# Inverter.net
KiCad netlist of a schematic drawn in Altium Designer
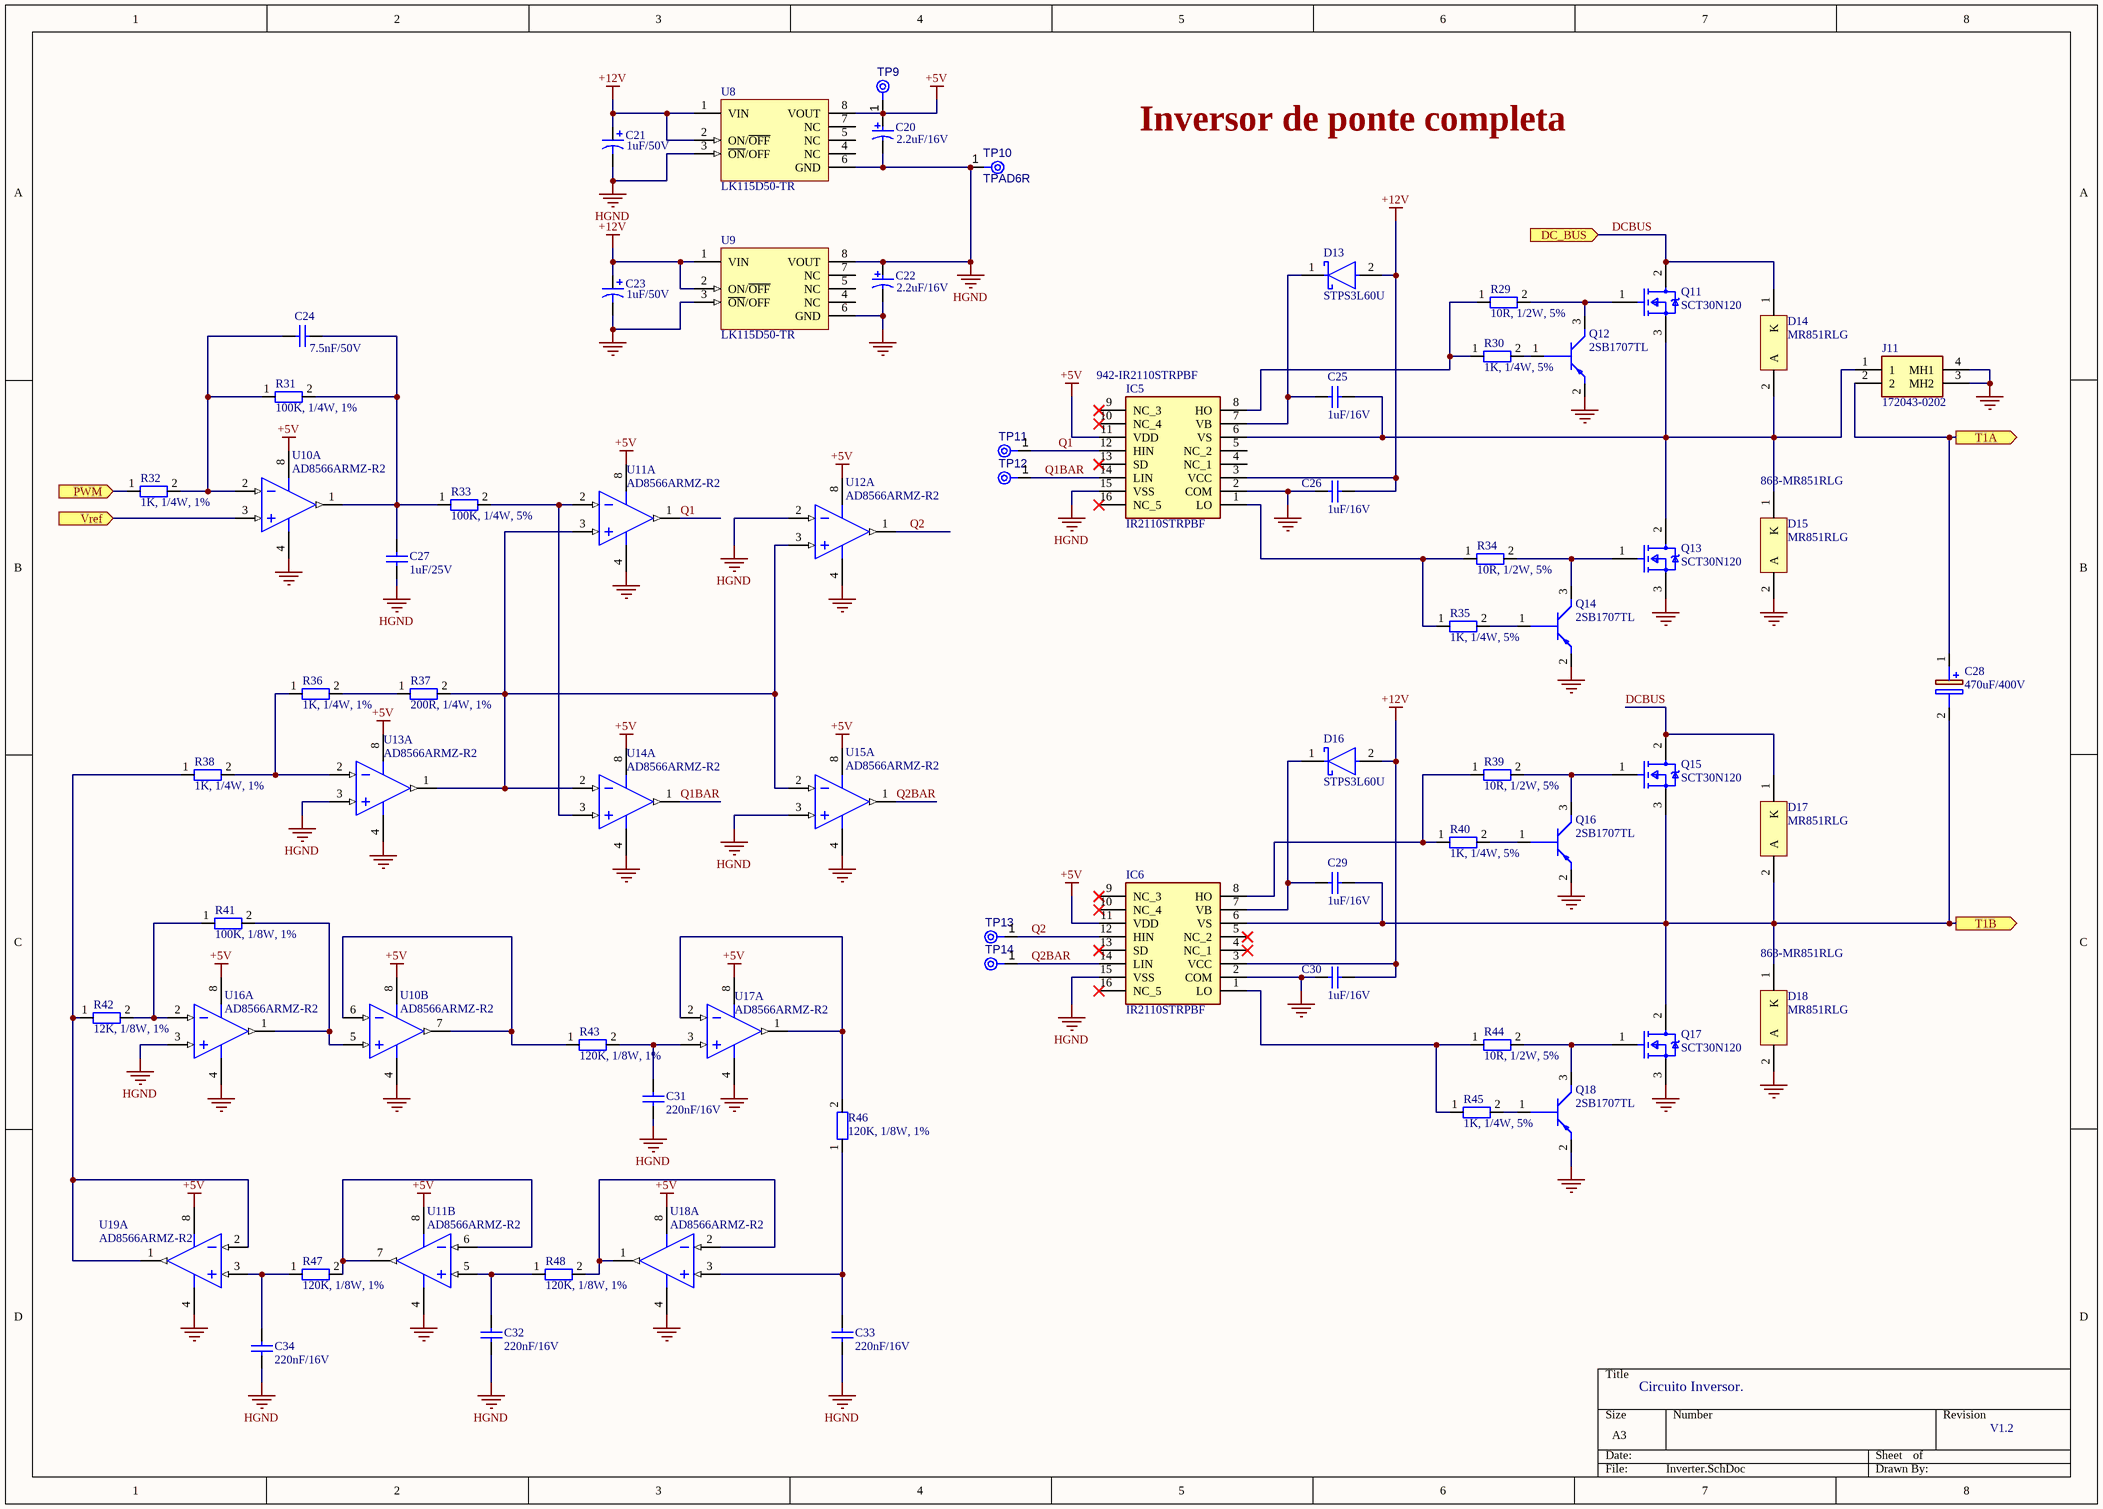
[diagram p0: Inverter.SchDoc]

(export (version "E")
  (design (tool "Eeschema 10.0.6"))
  (components
    (comp (ref "C20")
      (value "2.2uF/16V")
      (footprint "KEMT-T491-A_L")
      (description "Tantalum Capacitor, 2.2 uF, +/- 10%, 16 V, -55 to 125 degC, 2-Pin SMD, RoHS, Tape and Reel")
      (fields (field (name "VOLTAGE") "16VDC") (field (name "MANUFACTURER") "Kemet"))
      (libsource (lib "Altium Content Vault") (part "CAP-P-2"))
    )
    (comp (ref "C21")
      (value "1uF/50V")
      (footprint "C1206")
      (fields
        (field (name "MANUFACTURER") "KEMET")
        (field (name "MANUFACTURER PART NUMBER") "T491A105K050AT")
        (field (name "TOLERANCE") "10%")
        (field (name "PUBLISHER") "Altium Limited")
      )
      (libsource (lib "Miscellaneous Devices") (part "Cap Pol1"))
    )
    (comp (ref "C22")
      (value "2.2uF/16V")
      (footprint "KEMT-T491-A_L")
      (description "Tantalum Capacitor, 2.2 uF, +/- 10%, 16 V, -55 to 125 degC, 2-Pin SMD, RoHS, Tape and Reel")
      (fields (field (name "VOLTAGE") "16VDC") (field (name "MANUFACTURER") "Kemet"))
      (libsource (lib "Altium Content Vault") (part "CAP-P-2"))
    )
    (comp (ref "C23")
      (value "1uF/50V")
      (footprint "C1206")
      (fields
        (field (name "MANUFACTURER") "KEMET")
        (field (name "MANUFACTURER PART NUMBER") "T491A105K050AT")
        (field (name "TOLERANCE") "10%")
        (field (name "PUBLISHER") "Altium Limited")
      )
      (libsource (lib "Miscellaneous Devices") (part "Cap Pol1"))
    )
    (comp (ref "C24")
      (value "7.5nF/50V")
      (footprint "CAPC2013X135X45LL10T25")
      (fields
        (field (name "MANUFACTURER") "Murata")
        (field (name "PART NUMBER") "GRM21BR71H105KA12L")
        (field (name "MANUFACTURER PART NUMBER") "C0805C752FAGAC7210")
      )
      (libsource (lib "Altium Content Vault") (part "CAP"))
    )
    (comp (ref "C25")
      (value "1uF/16V")
      (footprint "CAPC2013X140X50ML20T25")
      (fields
        (field (name "PART NUMBER") "C0805C105Z4VACTU")
        (field (name "MANUFACTURER") "Kemet")
        (field (name "TOLERANCE") "80%")
      )
      (libsource (lib "Altium Content Vault") (part "CAP"))
    )
    (comp (ref "C26")
      (value "1uF/16V")
      (footprint "CAPC2013X140X50ML20T25")
      (fields
        (field (name "PART NUMBER") "C0805C105Z4VACTU")
        (field (name "MANUFACTURER") "Kemet")
        (field (name "TOLERANCE") "80%")
      )
      (libsource (lib "Altium Content Vault") (part "CAP"))
    )
    (comp (ref "C27")
      (value "1uF/25V")
      (footprint "CAPC2013X135X45LL10T25")
      (fields
        (field (name "MANUFACTURER") "KEMET")
        (field (name "MANUFACTURER PART NUMBER") "C0805C302K3GACTU")
        (field (name "TOLERANCE") "10%")
      )
      (libsource (lib "Altium Content Vault") (part "CAP"))
    )
    (comp (ref "C28")
      (value "470uF/400V")
      (footprint "PcbLib1:CAPPRD1000W210D3500H3700")
      (description "Capacitor Polarised")
      (fields
        (field (name "MANUFACTURER_PART_NUMBER") "MAL225966471E3")
        (field (name "MOUSER PART NUMBER") "594-MAL225966471E3")
      )
      (libsource (lib "*") (part "MAL225966471E3"))
    )
    (comp (ref "C29")
      (value "1uF/16V")
      (footprint "CAPC2013X140X50ML20T25")
      (fields
        (field (name "PART NUMBER") "C0805C105Z4VACTU")
        (field (name "MANUFACTURER") "Kemet")
        (field (name "TOLERANCE") "80%")
      )
      (libsource (lib "Altium Content Vault") (part "CAP"))
    )
    (comp (ref "C30")
      (value "1uF/16V")
      (footprint "CAPC2013X140X50ML20T25")
      (fields
        (field (name "PART NUMBER") "C0805C105Z4VACTU")
        (field (name "MANUFACTURER") "Kemet")
        (field (name "TOLERANCE") "80%")
      )
      (libsource (lib "Altium Content Vault") (part "CAP"))
    )
    (comp (ref "C31")
      (value "220nF/16V")
      (footprint "CAPC2013X135X45LL10T25")
      (fields (field (name "MANUFACTURER") "Murata") (field (name "PART NUMBER") "GRM21BR71H105KA12L"))
      (libsource (lib "Altium Content Vault") (part "CAP"))
    )
    (comp (ref "C32")
      (value "220nF/16V")
      (footprint "CAPC2013X135X45LL10T25")
      (fields (field (name "MANUFACTURER") "Murata") (field (name "PART NUMBER") "GRM21BR71H105KA12L"))
      (libsource (lib "Altium Content Vault") (part "CAP"))
    )
    (comp (ref "C33")
      (value "220nF/16V")
      (footprint "CAPC2013X135X45LL10T25")
      (fields (field (name "MANUFACTURER") "Murata") (field (name "PART NUMBER") "GRM21BR71H105KA12L"))
      (libsource (lib "Altium Content Vault") (part "CAP"))
    )
    (comp (ref "C34")
      (value "220nF/16V")
      (footprint "CAPC2013X135X45LL10T25")
      (fields (field (name "MANUFACTURER") "Murata") (field (name "PART NUMBER") "GRM21BR71H105KA12L"))
      (libsource (lib "Altium Content Vault") (part "CAP"))
    )
    (comp (ref "D13")
      (value "STPS3L60U")
      (footprint "FP-SMB-MFG")
      (description "DIODE SCHOTTKY 60V 3A SMB")
      (fields
        (field (name "OCTOPART") "https://octopart.com/stps3l60u-stmicroelectronics-334329")
        (field (name "MANUFACTURER") "STMicroelectronics")
      )
      (libsource (lib "Altium Content Vault") (part "fefb30dabb5d097ae2f038500735429"))
    )
    (comp (ref "D14")
      (value "MR851RLG")
      (footprint "ONSC-AXIAL_LEAD-2-267-05_V")
      (description "Fast Recovery Rectifier, 2-Pin Axial_Lead, Pb-Free, Tape and Reel")
      (fields (field (name "MANUFACTURER") "On Semiconductor"))
      (libsource (lib "Altium Content Vault") (part "ONSC-D-K1A2-2_A"))
    )
    (comp (ref "D15")
      (value "MR851RLG")
      (footprint "ONSC-AXIAL_LEAD-2-267-05_V")
      (description "Fast Recovery Rectifier, 2-Pin Axial_Lead, Pb-Free, Tape and Reel")
      (fields
        (field (name "MANUFACTURER") "On Semiconductor")
        (field (name "SUPPLIER PART NUMBER 1") "863-MR851RLG")
      )
      (libsource (lib "Altium Content Vault") (part "ONSC-D-K1A2-2_A"))
    )
    (comp (ref "D16")
      (value "STPS3L60U")
      (footprint "FP-SMB-MFG")
      (description "DIODE SCHOTTKY 60V 3A SMB")
      (fields
        (field (name "OCTOPART") "https://octopart.com/stps3l60u-stmicroelectronics-334329")
        (field (name "MANUFACTURER") "STMicroelectronics")
      )
      (libsource (lib "Altium Content Vault") (part "fefb30dabb5d097ae2f038500735429"))
    )
    (comp (ref "D17")
      (value "MR851RLG")
      (footprint "ONSC-AXIAL_LEAD-2-267-05_V")
      (description "Fast Recovery Rectifier, 2-Pin Axial_Lead, Pb-Free, Tape and Reel")
      (fields (field (name "MANUFACTURER") "On Semiconductor"))
      (libsource (lib "Altium Content Vault") (part "ONSC-D-K1A2-2_A"))
    )
    (comp (ref "D18")
      (value "MR851RLG")
      (footprint "ONSC-AXIAL_LEAD-2-267-05_V")
      (description "Fast Recovery Rectifier, 2-Pin Axial_Lead, Pb-Free, Tape and Reel")
      (fields
        (field (name "MANUFACTURER") "On Semiconductor")
        (field (name "SUPPLIER PART NUMBER 1") "863-MR851RLG")
      )
      (libsource (lib "Altium Content Vault") (part "ONSC-D-K1A2-2_A"))
    )
    (comp (ref "IC5")
      (value "IR2110STRPBF")
      (footprint "SOIC127P1032X265-16N")
      (description "MOSFET Driver 500 Volt 2.5A 2 Output Hi/Lo Side Non Input Volt 16-Pin SOIC W")
      (fields
        (field (name "MOUSER PART NUMBER") "942-IR2110STRPBF")
        (field (name "SUPPLIER PART NUMBER 1") "942-IR2110STRPBF")
        (field (name "MANUFACTURER") "International Rectifier")
      )
      (libsource (lib "pi2") (part "IR2110STRPBF"))
    )
    (comp (ref "IC6")
      (value "IR2110STRPBF")
      (footprint "SOIC127P1032X265-16N")
      (description "MOSFET Driver 500 Volt 2.5A 2 Output Hi/Lo Side Non Input Volt 16-Pin SOIC W")
      (fields
        (field (name "MOUSER PART NUMBER") "942-IR2110STRPBF")
        (field (name "MANUFACTURER") "International Rectifier")
      )
      (libsource (lib "pi2") (part "IR2110STRPBF"))
    )
    (comp (ref "J11")
      (value "172043-0202")
      (footprint "PcbLib1:1720430202")
      (description "CONN HDR 2POS 7.50MM R/A SLDR")
      (fields (field (name "MOUSER PART NUMBER") "538-172043-0202") (field (name "MANUFACTURER") "Molex"))
      (libsource (lib "pi2") (part "172043-0202"))
    )
    (comp (ref "Q11")
      (value "SCT30N120")
      (footprint "TO-247-3")
      (description "Trans MOSFET N-CH 1.2KV 45A 3-Pin HIP-247 Tube")
      (fields (field (name "MANUFACTURER") "STMicroelectronics"))
      (libsource (lib "pi2") (part "SCT30N120"))
    )
    (comp (ref "Q12")
      (value "2SB1707TL")
      (footprint "PcbLib1:SOT95P280X100-3N")
      (description "TRANS PNP 12V 4A TSMT3")
      (fields (field (name "MOUSER PART NUMBER") "755-2SB1707TL") (field (name "MANUFACTURER") "Rohm"))
      (libsource (lib "pi2") (part "2SB1707TL"))
    )
    (comp (ref "Q13")
      (value "SCT30N120")
      (footprint "TO-247-3")
      (description "Trans MOSFET N-CH 1.2KV 45A 3-Pin HIP-247 Tube")
      (fields (field (name "MANUFACTURER") "STMicroelectronics"))
      (libsource (lib "pi2") (part "SCT30N120"))
    )
    (comp (ref "Q14")
      (value "2SB1707TL")
      (footprint "PcbLib1:SOT95P280X100-3N")
      (description "TRANS PNP 12V 4A TSMT3")
      (fields (field (name "MOUSER PART NUMBER") "755-2SB1707TL") (field (name "MANUFACTURER") "Rohm"))
      (libsource (lib "pi2") (part "2SB1707TL"))
    )
    (comp (ref "Q15")
      (value "SCT30N120")
      (footprint "TO-247-3")
      (description "Trans MOSFET N-CH 1.2KV 45A 3-Pin HIP-247 Tube")
      (fields (field (name "MANUFACTURER") "STMicroelectronics"))
      (libsource (lib "pi2") (part "SCT30N120"))
    )
    (comp (ref "Q16")
      (value "2SB1707TL")
      (footprint "PcbLib1:SOT95P280X100-3N")
      (description "TRANS PNP 12V 4A TSMT3")
      (fields (field (name "MOUSER PART NUMBER") "755-2SB1707TL") (field (name "MANUFACTURER") "Rohm"))
      (libsource (lib "pi2") (part "2SB1707TL"))
    )
    (comp (ref "Q17")
      (value "SCT30N120")
      (footprint "TO-247-3")
      (description "Trans MOSFET N-CH 1.2KV 45A 3-Pin HIP-247 Tube")
      (fields (field (name "MANUFACTURER") "STMicroelectronics"))
      (libsource (lib "pi2") (part "SCT30N120"))
    )
    (comp (ref "Q18")
      (value "2SB1707TL")
      (footprint "PcbLib1:SOT95P280X100-3N")
      (description "TRANS PNP 12V 4A TSMT3")
      (fields (field (name "MOUSER PART NUMBER") "755-2SB1707TL") (field (name "MANUFACTURER") "Rohm"))
      (libsource (lib "pi2") (part "2SB1707TL"))
    )
    (comp (ref "R29")
      (value "10R, 1/2W, 5%")
      (footprint "RESC3216X60N")
      (description "Res Thick Film 0805 10 Ohm 5% 0.5W(1/2W) +/-200ppm/C Pad SMD Automotive T/R")
      (fields
        (field (name "MANUFACTURER") "Vishay Dale")
        (field (name "MANUFACTURER PART NUMBER") "CRCW080510R0JNEAHP")
      )
      (libsource (lib "pi2") (part "RES-1206"))
    )
    (comp (ref "R30")
      (value "1K, 1/4W, 5%")
      (footprint "PcbLib1:RES-0805")
      (description "Res Thick Film 0805 1K Ohm 5% 1/8W 100ppm/C Molded SMD SMD Paper T/R")
      (fields
        (field (name "MANUFACTURER_PART_NUMBER") "RC0805JR-131KL")
        (field (name "MOUSER PART NUMBER") "603-RC0805JR-131KL")
      )
      (libsource (lib "pi2") (part "Res-0805"))
    )
    (comp (ref "R31")
      (value "100K, 1/4W, 1%")
      (footprint "PcbLib1:RES-0805")
      (description "Thick Film Resistors 100K OHM 1%")
      (fields
        (field (name "MANUFACTURER_PART_NUMBER") "RC0805JR-131KL")
        (field (name "MOUSER PART NUMBER") "603-RC0805JR-131KL")
      )
      (libsource (lib "pi2") (part "Res-0805"))
    )
    (comp (ref "R32")
      (value "1K, 1/4W, 1%")
      (footprint "PcbLib1:RES-0805")
      (description "Res Thick Film 0805 1K Ohm 1% 1/8W 100ppm/C Molded SMD SMD Paper T/R")
      (fields
        (field (name "MANUFACTURER_PART_NUMBER") "RC0805JR-131KL")
        (field (name "MOUSER PART NUMBER") "603-RC0805JR-131KL")
      )
      (libsource (lib "pi2") (part "Res-0805"))
    )
    (comp (ref "R33")
      (value "100K, 1/4W, 5%")
      (footprint "PcbLib1:RES-0805")
      (description "Thick Film Resistors 100K OHM 1%")
      (fields
        (field (name "MANUFACTURER_PART_NUMBER") "RC0805JR-131KL")
        (field (name "MOUSER PART NUMBER") "603-RC0805JR-131KL")
      )
      (libsource (lib "pi2") (part "Res-0805"))
    )
    (comp (ref "R34")
      (value "10R, 1/2W, 5%")
      (footprint "RESC3216X60N")
      (description "Res Thick Film 0805 10 Ohm 5% 0.5W(1/2W) +/-200ppm/C Pad SMD Automotive T/R")
      (fields
        (field (name "MANUFACTURER") "Vishay Dale")
        (field (name "MANUFACTURER PART NUMBER") "CRCW080510R0JNEAHP")
      )
      (libsource (lib "pi2") (part "RES-1206"))
    )
    (comp (ref "R35")
      (value "1K, 1/4W, 5%")
      (footprint "PcbLib1:RES-0805")
      (description "Res Thick Film 0805 1K Ohm 5% 1/8W 100ppm/C Molded SMD SMD Paper T/R")
      (fields
        (field (name "MANUFACTURER_PART_NUMBER") "RC0805JR-131KL")
        (field (name "MOUSER PART NUMBER") "603-RC0805JR-131KL")
      )
      (libsource (lib "pi2") (part "Res-0805"))
    )
    (comp (ref "R36")
      (value "1K, 1/4W, 1%")
      (footprint "PcbLib1:RES-0805")
      (description "Res Thick Film 0805 1K Ohm 1% 1/8W 100ppm/C Molded SMD SMD Paper T/R")
      (fields
        (field (name "MANUFACTURER_PART_NUMBER") "RC0805JR-131KL")
        (field (name "MOUSER PART NUMBER") "603-RC0805JR-131KL")
      )
      (libsource (lib "pi2") (part "Res-0805"))
    )
    (comp (ref "R37")
      (value "200R, 1/4W, 1%")
      (footprint "PcbLib1:RES-0805")
      (description "Res Thick Film 2.0 x 1.2 mm 200 Ohm 1% 0.125W(1/8W) 100ppm/ C Molded SMD Paper T/R")
      (fields
        (field (name "MANUFACTURER_PART_NUMBER") "RC0805JR-131KL")
        (field (name "MOUSER PART NUMBER") "603-RC0805JR-131KL")
      )
      (libsource (lib "pi2") (part "Res-0805"))
    )
    (comp (ref "R38")
      (value "1K, 1/4W, 1%")
      (footprint "PcbLib1:RES-0805")
      (description "Res Thick Film 0805 1K Ohm 1% 1/8W 100ppm/C Molded SMD SMD Paper T/R")
      (fields
        (field (name "MANUFACTURER_PART_NUMBER") "RC0805JR-131KL")
        (field (name "MOUSER PART NUMBER") "603-RC0805JR-131KL")
      )
      (libsource (lib "pi2") (part "Res-0805"))
    )
    (comp (ref "R39")
      (value "10R, 1/2W, 5%")
      (footprint "RESC3216X60N")
      (description "Res Thick Film 0805 10 Ohm 5% 0.5W(1/2W) +/-200ppm/C Pad SMD Automotive T/R")
      (fields
        (field (name "MANUFACTURER") "Vishay Dale")
        (field (name "MANUFACTURER PART NUMBER") "CRCW080510R0JNEAHP")
      )
      (libsource (lib "pi2") (part "RES-1206"))
    )
    (comp (ref "R40")
      (value "1K, 1/4W, 5%")
      (footprint "PcbLib1:RES-0805")
      (description "Res Thick Film 0805 1K Ohm 5% 1/8W 100ppm/C Molded SMD SMD Paper T/R")
      (fields
        (field (name "MANUFACTURER_PART_NUMBER") "RC0805JR-131KL")
        (field (name "MOUSER PART NUMBER") "603-RC0805JR-131KL")
      )
      (libsource (lib "pi2") (part "Res-0805"))
    )
    (comp (ref "R41")
      (value "100K, 1/8W, 1%")
      (footprint "PcbLib1:RES-0805")
      (description "Thick Film Resistors 100K OHM 1%")
      (fields
        (field (name "MANUFACTURER_PART_NUMBER") "RC0805JR-131KL")
        (field (name "MOUSER PART NUMBER") "603-RC0805JR-131KL")
      )
      (libsource (lib "pi2") (part "Res-0805"))
    )
    (comp (ref "R42")
      (value "12K, 1/8W, 1%")
      (footprint "PcbLib1:RES-0805")
      (description "Res Thick Film 0805 12K Ohm 1% 0.125W(1/8W) ±100ppm/C Molded SMD Paper T/R")
      (fields
        (field (name "MANUFACTURER_PART_NUMBER") "RC0805JR-131KL")
        (field (name "MOUSER PART NUMBER") "603-RC0805JR-131KL")
      )
      (libsource (lib "pi2") (part "Res-0805"))
    )
    (comp (ref "R43")
      (value "120K, 1/8W, 1%")
      (footprint "PcbLib1:RES-0805")
      (description "YAGEO - RC0805FR-07120KL - RES, 120K, 1%, 0.125W, 0805, THICK FILM")
      (fields
        (field (name "MANUFACTURER_PART_NUMBER") "RC0805JR-131KL")
        (field (name "MOUSER PART NUMBER") "603-RC0805JR-131KL")
      )
      (libsource (lib "pi2") (part "Res-0805"))
    )
    (comp (ref "R44")
      (value "10R, 1/2W, 5%")
      (footprint "RESC3216X60N")
      (description "Res Thick Film 0805 10 Ohm 5% 0.5W(1/2W) +/-200ppm/C Pad SMD Automotive T/R")
      (fields
        (field (name "MANUFACTURER") "Vishay Dale")
        (field (name "MANUFACTURER PART NUMBER") "CRCW080510R0JNEAHP")
      )
      (libsource (lib "pi2") (part "RES-1206"))
    )
    (comp (ref "R45")
      (value "1K, 1/4W, 5%")
      (footprint "PcbLib1:RES-0805")
      (description "Res Thick Film 0805 1K Ohm 5% 1/8W 100ppm/C Molded SMD SMD Paper T/R")
      (fields
        (field (name "MANUFACTURER_PART_NUMBER") "RC0805JR-131KL")
        (field (name "MOUSER PART NUMBER") "603-RC0805JR-131KL")
      )
      (libsource (lib "pi2") (part "Res-0805"))
    )
    (comp (ref "R46")
      (value "120K, 1/8W, 1%")
      (footprint "PcbLib1:RES-0805")
      (description "YAGEO - RC0805FR-07120KL - RES, 120K, 1%, 0.125W, 0805, THICK FILM")
      (fields
        (field (name "MANUFACTURER_PART_NUMBER") "RC0805JR-131KL")
        (field (name "MOUSER PART NUMBER") "603-RC0805JR-131KL")
      )
      (libsource (lib "") (part "Res-0805_1"))
    )
    (comp (ref "R47")
      (value "120K, 1/8W, 1%")
      (footprint "PcbLib1:RES-0805")
      (description "YAGEO - RC0805FR-07120KL - RES, 120K, 1%, 0.125W, 0805, THICK FILM")
      (fields
        (field (name "MANUFACTURER_PART_NUMBER") "RC0805JR-131KL")
        (field (name "MOUSER PART NUMBER") "603-RC0805JR-131KL")
      )
      (libsource (lib "pi2") (part "Res-0805"))
    )
    (comp (ref "R48")
      (value "120K, 1/8W, 1%")
      (footprint "PcbLib1:RES-0805")
      (description "YAGEO - RC0805FR-07120KL - RES, 120K, 1%, 0.125W, 0805, THICK FILM")
      (fields
        (field (name "MANUFACTURER_PART_NUMBER") "RC0805JR-131KL")
        (field (name "MOUSER PART NUMBER") "603-RC0805JR-131KL")
      )
      (libsource (lib "pi2") (part "Res-0805"))
    )
    (comp (ref "TP9")
      (value "TPAD6R")
      (footprint "TP06R")
      (description "0.6mm round")
      (libsource (lib "PI2") (part "CMP-001-0001-4"))
    )
    (comp (ref "TP10")
      (value "TPAD6R")
      (footprint "TP06R")
      (description "0.6mm round")
      (libsource (lib "PI2") (part "CMP-001-0001-4"))
    )
    (comp (ref "TP11")
      (value "TPAD6R")
      (footprint "TP06R")
      (description "0.6mm round")
      (libsource (lib "PI2") (part "CMP-001-0001-4"))
    )
    (comp (ref "TP12")
      (value "TPAD6R")
      (footprint "TP06R")
      (description "0.6mm round")
      (libsource (lib "PI2") (part "CMP-001-0001-4"))
    )
    (comp (ref "TP13")
      (value "TPAD6R")
      (footprint "TP06R")
      (description "0.6mm round")
      (libsource (lib "PI2") (part "CMP-001-0001-4"))
    )
    (comp (ref "TP14")
      (value "TPAD6R")
      (footprint "TP06R")
      (description "0.6mm round")
      (libsource (lib "PI2") (part "CMP-001-0001-4"))
    )
    (comp (ref "U8")
      (value "LK115D50-TR")
      (footprint "SO8_M")
      (description "100mA, Very Low Drop (0.2V) with Inhibit Voltage Regulator, 5V, 8-Pin SO, Tape and Reel")
      (fields (field (name "MANUFACTURER") "STMicroelectronics"))
      (libsource (lib "Altium Content Vault") (part "PM-REG-LK115D-IL8"))
    )
    (comp (ref "U9")
      (value "LK115D50-TR")
      (footprint "SO8_M")
      (description "100mA, Very Low Drop (0.2V) with Inhibit Voltage Regulator, 5V, 8-Pin SO, Tape and Reel")
      (fields (field (name "MANUFACTURER") "STMicroelectronics"))
      (libsource (lib "Altium Content Vault") (part "PM-REG-LK115D-IL8"))
    )
    (comp (ref "U10")
      (value "AD8566ARMZ-R2")
      (footprint "ADI-RM-8_L")
      (fields (field (name "MANUFACTURER") "Analog Devices") (field (name "GENERIC PART NUMBER") "AD8566"))
      (libsource (lib "Altium Content Vault") (part "ADI-ADA4000-2-X-8"))
    )
    (comp (ref "U11")
      (value "AD8566ARMZ-R2")
      (footprint "ADI-RM-8_L")
      (fields (field (name "MANUFACTURER") "Analog Devices") (field (name "GENERIC PART NUMBER") "AD8566"))
      (libsource (lib "Altium Content Vault") (part "ADI-ADA4000-2-X-8"))
    )
    (comp (ref "U12")
      (value "AD8566ARMZ-R2")
      (footprint "ADI-RM-8_L")
      (fields (field (name "MANUFACTURER") "Analog Devices") (field (name "GENERIC PART NUMBER") "AD8566"))
      (libsource (lib "Altium Content Vault") (part "ADI-ADA4000-2-X-8"))
    )
    (comp (ref "U13")
      (value "AD8566ARMZ-R2")
      (footprint "ADI-RM-8_L")
      (fields (field (name "MANUFACTURER") "Analog Devices") (field (name "GENERIC PART NUMBER") "AD8566"))
      (libsource (lib "Altium Content Vault") (part "ADI-ADA4000-2-X-8"))
    )
    (comp (ref "U14")
      (value "AD8566ARMZ-R2")
      (footprint "ADI-RM-8_L")
      (fields (field (name "MANUFACTURER") "Analog Devices") (field (name "GENERIC PART NUMBER") "AD8566"))
      (libsource (lib "Altium Content Vault") (part "ADI-ADA4000-2-X-8"))
    )
    (comp (ref "U15")
      (value "AD8566ARMZ-R2")
      (footprint "ADI-RM-8_L")
      (fields (field (name "MANUFACTURER") "Analog Devices") (field (name "GENERIC PART NUMBER") "AD8566"))
      (libsource (lib "Altium Content Vault") (part "ADI-ADA4000-2-X-8"))
    )
    (comp (ref "U16")
      (value "AD8566ARMZ-R2")
      (footprint "ADI-RM-8_L")
      (fields (field (name "MANUFACTURER") "Analog Devices") (field (name "GENERIC PART NUMBER") "AD8566"))
      (libsource (lib "Altium Content Vault") (part "ADI-ADA4000-2-X-8"))
    )
    (comp (ref "U17")
      (value "AD8566ARMZ-R2")
      (footprint "ADI-RM-8_L")
      (fields (field (name "MANUFACTURER") "Analog Devices") (field (name "GENERIC PART NUMBER") "AD8566"))
      (libsource (lib "Altium Content Vault") (part "ADI-ADA4000-2-X-8"))
    )
    (comp (ref "U18")
      (value "AD8566ARMZ-R2")
      (footprint "ADI-RM-8_L")
      (fields (field (name "MANUFACTURER") "Analog Devices") (field (name "GENERIC PART NUMBER") "AD8566"))
      (libsource (lib "Altium Content Vault") (part "ADI-ADA4000-2-X-8"))
    )
    (comp (ref "U19")
      (value "AD8566ARMZ-R2")
      (footprint "ADI-RM-8_L")
      (fields (field (name "MANUFACTURER") "Analog Devices") (field (name "GENERIC PART NUMBER") "AD8566"))
      (libsource (lib "Altium Content Vault") (part "ADI-ADA4000-2-X-8"))
    )
  )
  (nets
    (net (code "1") (name "+5V") (class "Default")
      (node (ref "C20") (pin "1") (pinfunction "1_1") (pintype "passive"))
      (node (ref "IC5") (pin "11") (pinfunction "VDD_11") (pintype "passive"))
      (node (ref "IC6") (pin "11") (pinfunction "VDD_11") (pintype "passive"))
      (node (ref "TP9") (pin "1") (pinfunction "TP_1") (pintype "passive"))
      (node (ref "U10") (pin "8") (pinfunction "+V_8") (pintype "power_in"))
      (node (ref "U11") (pin "8") (pinfunction "+V_8") (pintype "power_in"))
      (node (ref "U12") (pin "8") (pinfunction "+V_8") (pintype "power_in"))
      (node (ref "U13") (pin "8") (pinfunction "+V_8") (pintype "power_in"))
      (node (ref "U14") (pin "8") (pinfunction "+V_8") (pintype "power_in"))
      (node (ref "U15") (pin "8") (pinfunction "+V_8") (pintype "power_in"))
      (node (ref "U16") (pin "8") (pinfunction "+V_8") (pintype "power_in"))
      (node (ref "U17") (pin "8") (pinfunction "+V_8") (pintype "power_in"))
      (node (ref "U18") (pin "8") (pinfunction "+V_8") (pintype "power_in"))
      (node (ref "U19") (pin "8") (pinfunction "+V_8") (pintype "power_in"))
      (node (ref "U8") (pin "8") (pinfunction "VOUT_8") (pintype "power_in"))
    )
    (net (code "2") (name "+12V") (class "Default")
      (node (ref "C21") (pin "1") (pinfunction "1_1") (pintype "passive"))
      (node (ref "C23") (pin "1") (pinfunction "1_1") (pintype "passive"))
      (node (ref "C26") (pin "2") (pinfunction "2_2") (pintype "passive"))
      (node (ref "C30") (pin "1") (pinfunction "1_1") (pintype "passive"))
      (node (ref "D13") (pin "2") (pinfunction "A_2") (pintype "passive"))
      (node (ref "D16") (pin "2") (pinfunction "A_2") (pintype "passive"))
      (node (ref "IC5") (pin "3") (pinfunction "VCC_3") (pintype "passive"))
      (node (ref "IC6") (pin "3") (pinfunction "VCC_3") (pintype "passive"))
      (node (ref "U8") (pin "1") (pinfunction "VIN_1") (pintype "power_in"))
      (node (ref "U8") (pin "2") (pinfunction "ON/~{OFF}_2") (pintype "input"))
      (node (ref "U9") (pin "1") (pinfunction "VIN_1") (pintype "power_in"))
      (node (ref "U9") (pin "2") (pinfunction "ON/~{OFF}_2") (pintype "input"))
    )
    (net (code "3") (name "/DCBUS") (class "Default")
      (node (ref "D14") (pin "1") (pinfunction "K_1") (pintype "passive"))
      (node (ref "D17") (pin "1") (pinfunction "K_1") (pintype "passive"))
      (node (ref "Q11") (pin "2") (pinfunction "D_2") (pintype "passive"))
      (node (ref "Q15") (pin "2") (pinfunction "D_2") (pintype "passive"))
    )
    (net (code "4") (name "/PWM") (class "Default")
      (node (ref "R32") (pin "1") (pinfunction "1_1") (pintype "passive"))
    )
    (net (code "5") (name "/Q1") (class "Default")
      (node (ref "IC5") (pin "12") (pinfunction "HIN_12") (pintype "passive"))
      (node (ref "TP11") (pin "1") (pinfunction "TP_1") (pintype "passive"))
      (node (ref "U11") (pin "1") (pinfunction "OUT_A_1") (pintype "output"))
    )
    (net (code "6") (name "/Q1BAR") (class "Default")
      (node (ref "IC5") (pin "14") (pinfunction "LIN_14") (pintype "passive"))
      (node (ref "TP12") (pin "1") (pinfunction "TP_1") (pintype "passive"))
      (node (ref "U14") (pin "1") (pinfunction "OUT_A_1") (pintype "output"))
    )
    (net (code "7") (name "/Q2") (class "Default")
      (node (ref "IC6") (pin "12") (pinfunction "HIN_12") (pintype "passive"))
      (node (ref "TP13") (pin "1") (pinfunction "TP_1") (pintype "passive"))
      (node (ref "U12") (pin "1") (pinfunction "OUT_A_1") (pintype "output"))
    )
    (net (code "8") (name "/Q2BAR") (class "Default")
      (node (ref "IC6") (pin "14") (pinfunction "LIN_14") (pintype "passive"))
      (node (ref "TP14") (pin "1") (pinfunction "TP_1") (pintype "passive"))
      (node (ref "U15") (pin "1") (pinfunction "OUT_A_1") (pintype "output"))
    )
    (net (code "9") (name "/T1A") (class "Default")
      (node (ref "C28") (pin "1") (pinfunction "+_1") (pintype "passive"))
      (node (ref "J11") (pin "2") (pinfunction "2_2") (pintype "passive"))
    )
    (net (code "10") (name "/T1B") (class "Default")
      (node (ref "C28") (pin "2") (pinfunction "-_2") (pintype "passive"))
      (node (ref "C29") (pin "1") (pinfunction "1_1") (pintype "passive"))
      (node (ref "D17") (pin "2") (pinfunction "A_2") (pintype "passive"))
      (node (ref "D18") (pin "1") (pinfunction "K_1") (pintype "passive"))
      (node (ref "IC6") (pin "6") (pinfunction "VS_6") (pintype "passive"))
      (node (ref "Q15") (pin "3") (pinfunction "S_3") (pintype "passive"))
      (node (ref "Q17") (pin "2") (pinfunction "D_2") (pintype "passive"))
    )
    (net (code "11") (name "/Vref") (class "Default")
      (node (ref "U10") (pin "3") (pinfunction "+IN_A_3") (pintype "input"))
    )
    (net (code "12") (name "GND") (class "Default")
      (node (ref "C22") (pin "2") (pinfunction "2_2") (pintype "passive"))
      (node (ref "C23") (pin "2") (pinfunction "2_2") (pintype "passive"))
      (node (ref "C26") (pin "1") (pinfunction "1_1") (pintype "passive"))
      (node (ref "C30") (pin "2") (pinfunction "2_2") (pintype "passive"))
      (node (ref "D15") (pin "2") (pinfunction "A_2") (pintype "passive"))
      (node (ref "D18") (pin "2") (pinfunction "A_2") (pintype "passive"))
      (node (ref "IC5") (pin "2") (pinfunction "COM_2") (pintype "passive"))
      (node (ref "IC6") (pin "2") (pinfunction "COM_2") (pintype "passive"))
      (node (ref "J11") (pin "3") (pinfunction "MH2_3") (pintype "passive"))
      (node (ref "J11") (pin "4") (pinfunction "MH1_4") (pintype "passive"))
      (node (ref "Q12") (pin "2") (pinfunction "E_2") (pintype "passive"))
      (node (ref "Q13") (pin "3") (pinfunction "S_3") (pintype "passive"))
      (node (ref "Q14") (pin "2") (pinfunction "E_2") (pintype "passive"))
      (node (ref "Q16") (pin "2") (pinfunction "E_2") (pintype "passive"))
      (node (ref "Q17") (pin "3") (pinfunction "S_3") (pintype "passive"))
      (node (ref "Q18") (pin "2") (pinfunction "E_2") (pintype "passive"))
      (node (ref "U10") (pin "4") (pinfunction "-V_4") (pintype "power_in"))
      (node (ref "U11") (pin "4") (pinfunction "-V_4") (pintype "power_in"))
      (node (ref "U12") (pin "4") (pinfunction "-V_4") (pintype "power_in"))
      (node (ref "U13") (pin "4") (pinfunction "-V_4") (pintype "power_in"))
      (node (ref "U14") (pin "4") (pinfunction "-V_4") (pintype "power_in"))
      (node (ref "U15") (pin "4") (pinfunction "-V_4") (pintype "power_in"))
      (node (ref "U16") (pin "4") (pinfunction "-V_4") (pintype "power_in"))
      (node (ref "U17") (pin "4") (pinfunction "-V_4") (pintype "power_in"))
      (node (ref "U18") (pin "4") (pinfunction "-V_4") (pintype "power_in"))
      (node (ref "U19") (pin "4") (pinfunction "-V_4") (pintype "power_in"))
      (node (ref "U9") (pin "3") (pinfunction "~{ON}/OFF_3") (pintype "input"))
      (node (ref "U9") (pin "6") (pinfunction "GND_6") (pintype "power_in"))
    )
    (net (code "13") (name "HGND") (class "Default")
      (node (ref "C20") (pin "2") (pinfunction "2_2") (pintype "passive"))
      (node (ref "C21") (pin "2") (pinfunction "2_2") (pintype "passive"))
      (node (ref "C22") (pin "1") (pinfunction "1_1") (pintype "passive"))
      (node (ref "C27") (pin "1") (pinfunction "1_1") (pintype "passive"))
      (node (ref "C31") (pin "1") (pinfunction "1_1") (pintype "passive"))
      (node (ref "C32") (pin "1") (pinfunction "1_1") (pintype "passive"))
      (node (ref "C33") (pin "1") (pinfunction "1_1") (pintype "passive"))
      (node (ref "C34") (pin "1") (pinfunction "1_1") (pintype "passive"))
      (node (ref "IC5") (pin "15") (pinfunction "VSS_15") (pintype "passive"))
      (node (ref "IC6") (pin "15") (pinfunction "VSS_15") (pintype "passive"))
      (node (ref "TP10") (pin "1") (pinfunction "TP_1") (pintype "passive"))
      (node (ref "U12") (pin "2") (pinfunction "-IN_A_2") (pintype "input"))
      (node (ref "U13") (pin "3") (pinfunction "+IN_A_3") (pintype "input"))
      (node (ref "U15") (pin "3") (pinfunction "+IN_A_3") (pintype "input"))
      (node (ref "U16") (pin "3") (pinfunction "+IN_A_3") (pintype "input"))
      (node (ref "U8") (pin "3") (pinfunction "~{ON}/OFF_3") (pintype "input"))
      (node (ref "U8") (pin "6") (pinfunction "GND_6") (pintype "power_in"))
      (node (ref "U9") (pin "8") (pinfunction "VOUT_8") (pintype "power_in"))
    )
    (net (code "14") (name "Net-(D13-K)") (class "Default")
      (node (ref "C25") (pin "1") (pinfunction "1_1") (pintype "passive"))
      (node (ref "D13") (pin "1") (pinfunction "K_1") (pintype "passive"))
      (node (ref "IC5") (pin "7") (pinfunction "VB_7") (pintype "passive"))
    )
    (net (code "15") (name "Net-(D14-A)") (class "Default")
      (node (ref "C25") (pin "2") (pinfunction "2_2") (pintype "passive"))
      (node (ref "D14") (pin "2") (pinfunction "A_2") (pintype "passive"))
      (node (ref "D15") (pin "1") (pinfunction "K_1") (pintype "passive"))
      (node (ref "IC5") (pin "6") (pinfunction "VS_6") (pintype "passive"))
      (node (ref "J11") (pin "1") (pinfunction "1_1") (pintype "passive"))
      (node (ref "Q11") (pin "3") (pinfunction "S_3") (pintype "passive"))
      (node (ref "Q13") (pin "2") (pinfunction "D_2") (pintype "passive"))
    )
    (net (code "16") (name "Net-(D16-K)") (class "Default")
      (node (ref "C29") (pin "2") (pinfunction "2_2") (pintype "passive"))
      (node (ref "D16") (pin "1") (pinfunction "K_1") (pintype "passive"))
      (node (ref "IC6") (pin "7") (pinfunction "VB_7") (pintype "passive"))
    )
    (net (code "17") (name "Net-(IC5-HO)") (class "Default")
      (node (ref "IC5") (pin "8") (pinfunction "HO_8") (pintype "passive"))
      (node (ref "R29") (pin "1") (pinfunction "1_1") (pintype "passive"))
      (node (ref "R30") (pin "1") (pinfunction "1_1") (pintype "passive"))
    )
    (net (code "18") (name "Net-(IC5-LO)") (class "Default")
      (node (ref "IC5") (pin "1") (pinfunction "LO_1") (pintype "passive"))
      (node (ref "R34") (pin "1") (pinfunction "1_1") (pintype "passive"))
      (node (ref "R35") (pin "1") (pinfunction "1_1") (pintype "passive"))
    )
    (net (code "19") (name "Net-(IC6-HO)") (class "Default")
      (node (ref "IC6") (pin "8") (pinfunction "HO_8") (pintype "passive"))
      (node (ref "R39") (pin "1") (pinfunction "1_1") (pintype "passive"))
      (node (ref "R40") (pin "1") (pinfunction "1_1") (pintype "passive"))
    )
    (net (code "20") (name "Net-(IC6-LO)") (class "Default")
      (node (ref "IC6") (pin "1") (pinfunction "LO_1") (pintype "passive"))
      (node (ref "R44") (pin "1") (pinfunction "1_1") (pintype "passive"))
      (node (ref "R45") (pin "1") (pinfunction "1_1") (pintype "passive"))
    )
    (net (code "21") (name "Net-(Q11-G)") (class "Default")
      (node (ref "Q11") (pin "1") (pinfunction "G_1") (pintype "passive"))
      (node (ref "Q12") (pin "3") (pinfunction "C_3") (pintype "passive"))
      (node (ref "R29") (pin "2") (pinfunction "2_2") (pintype "passive"))
    )
    (net (code "22") (name "Net-(Q12-B)") (class "Default")
      (node (ref "Q12") (pin "1") (pinfunction "B_1") (pintype "passive"))
      (node (ref "R30") (pin "2") (pinfunction "2_2") (pintype "passive"))
    )
    (net (code "23") (name "Net-(Q13-G)") (class "Default")
      (node (ref "Q13") (pin "1") (pinfunction "G_1") (pintype "passive"))
      (node (ref "Q14") (pin "3") (pinfunction "C_3") (pintype "passive"))
      (node (ref "R34") (pin "2") (pinfunction "2_2") (pintype "passive"))
    )
    (net (code "24") (name "Net-(Q14-B)") (class "Default")
      (node (ref "Q14") (pin "1") (pinfunction "B_1") (pintype "passive"))
      (node (ref "R35") (pin "2") (pinfunction "2_2") (pintype "passive"))
    )
    (net (code "25") (name "Net-(Q15-G)") (class "Default")
      (node (ref "Q15") (pin "1") (pinfunction "G_1") (pintype "passive"))
      (node (ref "Q16") (pin "3") (pinfunction "C_3") (pintype "passive"))
      (node (ref "R39") (pin "2") (pinfunction "2_2") (pintype "passive"))
    )
    (net (code "26") (name "Net-(Q16-B)") (class "Default")
      (node (ref "Q16") (pin "1") (pinfunction "B_1") (pintype "passive"))
      (node (ref "R40") (pin "2") (pinfunction "2_2") (pintype "passive"))
    )
    (net (code "27") (name "Net-(Q17-G)") (class "Default")
      (node (ref "Q17") (pin "1") (pinfunction "G_1") (pintype "passive"))
      (node (ref "Q18") (pin "3") (pinfunction "C_3") (pintype "passive"))
      (node (ref "R44") (pin "2") (pinfunction "2_2") (pintype "passive"))
    )
    (net (code "28") (name "Net-(Q18-B)") (class "Default")
      (node (ref "Q18") (pin "1") (pinfunction "B_1") (pintype "passive"))
      (node (ref "R45") (pin "2") (pinfunction "2_2") (pintype "passive"))
    )
    (net (code "29") (name "Net-(R36-Pad2)") (class "Default")
      (node (ref "R36") (pin "2") (pinfunction "2_2") (pintype "passive"))
      (node (ref "R37") (pin "1") (pinfunction "1_1") (pintype "passive"))
    )
    (net (code "30") (name "Net-(U10A--IN_A)") (class "Default")
      (node (ref "C24") (pin "2") (pinfunction "2_2") (pintype "passive"))
      (node (ref "R31") (pin "1") (pinfunction "1_1") (pintype "passive"))
      (node (ref "R32") (pin "2") (pinfunction "2_2") (pintype "passive"))
      (node (ref "U10") (pin "2") (pinfunction "-IN_A_2") (pintype "input"))
    )
    (net (code "31") (name "Net-(U10A-OUT_A)") (class "Default")
      (node (ref "C24") (pin "1") (pinfunction "1_1") (pintype "passive"))
      (node (ref "C27") (pin "2") (pinfunction "2_2") (pintype "passive"))
      (node (ref "R31") (pin "2") (pinfunction "2_2") (pintype "passive"))
      (node (ref "R33") (pin "1") (pinfunction "1_1") (pintype "passive"))
      (node (ref "U10") (pin "1") (pinfunction "OUT_A_1") (pintype "output"))
    )
    (net (code "32") (name "Net-(U10B-+IN_B)") (class "Default")
      (node (ref "R41") (pin "2") (pinfunction "2_2") (pintype "passive"))
      (node (ref "U10") (pin "5") (pinfunction "+IN_B_5") (pintype "input"))
      (node (ref "U16") (pin "1") (pinfunction "OUT_A_1") (pintype "output"))
    )
    (net (code "33") (name "Net-(U10B--IN_B)") (class "Default")
      (node (ref "R43") (pin "1") (pinfunction "1_1") (pintype "passive"))
      (node (ref "U10") (pin "6") (pinfunction "-IN_B_6") (pintype "input"))
      (node (ref "U10") (pin "7") (pinfunction "OUT_B_7") (pintype "output"))
    )
    (net (code "34") (name "Net-(U11A-+IN_A)") (class "Default")
      (node (ref "R37") (pin "2") (pinfunction "2_2") (pintype "passive"))
      (node (ref "U11") (pin "3") (pinfunction "+IN_A_3") (pintype "input"))
      (node (ref "U12") (pin "3") (pinfunction "+IN_A_3") (pintype "input"))
      (node (ref "U13") (pin "1") (pinfunction "OUT_A_1") (pintype "output"))
      (node (ref "U14") (pin "2") (pinfunction "-IN_A_2") (pintype "input"))
      (node (ref "U15") (pin "2") (pinfunction "-IN_A_2") (pintype "input"))
    )
    (net (code "35") (name "Net-(U11A--IN_A)") (class "Default")
      (node (ref "R33") (pin "2") (pinfunction "2_2") (pintype "passive"))
      (node (ref "U11") (pin "2") (pinfunction "-IN_A_2") (pintype "input"))
      (node (ref "U14") (pin "3") (pinfunction "+IN_A_3") (pintype "input"))
    )
    (net (code "36") (name "Net-(U11B-+IN_B)") (class "Default")
      (node (ref "C32") (pin "2") (pinfunction "2_2") (pintype "passive"))
      (node (ref "R48") (pin "1") (pinfunction "1_1") (pintype "passive"))
      (node (ref "U11") (pin "5") (pinfunction "+IN_B_5") (pintype "input"))
    )
    (net (code "37") (name "Net-(U11B--IN_B)") (class "Default")
      (node (ref "R47") (pin "2") (pinfunction "2_2") (pintype "passive"))
      (node (ref "U11") (pin "6") (pinfunction "-IN_B_6") (pintype "input"))
      (node (ref "U11") (pin "7") (pinfunction "OUT_B_7") (pintype "output"))
    )
    (net (code "38") (name "Net-(U13A--IN_A)") (class "Default")
      (node (ref "R36") (pin "1") (pinfunction "1_1") (pintype "passive"))
      (node (ref "R38") (pin "2") (pinfunction "2_2") (pintype "passive"))
      (node (ref "U13") (pin "2") (pinfunction "-IN_A_2") (pintype "input"))
    )
    (net (code "39") (name "Net-(U16A--IN_A)") (class "Default")
      (node (ref "R41") (pin "1") (pinfunction "1_1") (pintype "passive"))
      (node (ref "R42") (pin "2") (pinfunction "2_2") (pintype "passive"))
      (node (ref "U16") (pin "2") (pinfunction "-IN_A_2") (pintype "input"))
    )
    (net (code "40") (name "Net-(U17A-+IN_A)") (class "Default")
      (node (ref "C31") (pin "2") (pinfunction "2_2") (pintype "passive"))
      (node (ref "R43") (pin "2") (pinfunction "2_2") (pintype "passive"))
      (node (ref "U17") (pin "3") (pinfunction "+IN_A_3") (pintype "input"))
    )
    (net (code "41") (name "Net-(U17A--IN_A)") (class "Default")
      (node (ref "R46") (pin "2") (pinfunction "2_2") (pintype "passive"))
      (node (ref "U17") (pin "1") (pinfunction "OUT_A_1") (pintype "output"))
      (node (ref "U17") (pin "2") (pinfunction "-IN_A_2") (pintype "input"))
    )
    (net (code "42") (name "Net-(U18A-+IN_A)") (class "Default")
      (node (ref "C33") (pin "2") (pinfunction "2_2") (pintype "passive"))
      (node (ref "R46") (pin "1") (pinfunction "1_1") (pintype "passive"))
      (node (ref "U18") (pin "3") (pinfunction "+IN_A_3") (pintype "input"))
    )
    (net (code "43") (name "Net-(U18A--IN_A)") (class "Default")
      (node (ref "R48") (pin "2") (pinfunction "2_2") (pintype "passive"))
      (node (ref "U18") (pin "1") (pinfunction "OUT_A_1") (pintype "output"))
      (node (ref "U18") (pin "2") (pinfunction "-IN_A_2") (pintype "input"))
    )
    (net (code "44") (name "Net-(U19A-+IN_A)") (class "Default")
      (node (ref "C34") (pin "2") (pinfunction "2_2") (pintype "passive"))
      (node (ref "R47") (pin "1") (pinfunction "1_1") (pintype "passive"))
      (node (ref "U19") (pin "3") (pinfunction "+IN_A_3") (pintype "input"))
    )
    (net (code "45") (name "Net-(U19A--IN_A)") (class "Default")
      (node (ref "R38") (pin "1") (pinfunction "1_1") (pintype "passive"))
      (node (ref "R42") (pin "1") (pinfunction "1_1") (pintype "passive"))
      (node (ref "U19") (pin "1") (pinfunction "OUT_A_1") (pintype "output"))
      (node (ref "U19") (pin "2") (pinfunction "-IN_A_2") (pintype "input"))
    )
    (net (code "46") (name "unconnected-(IC5-NC_1-Pad4)") (class "Default")
      (node (ref "IC5") (pin "4") (pinfunction "NC_1_4") (pintype "passive"))
    )
    (net (code "47") (name "unconnected-(IC5-NC_2-Pad5)") (class "Default")
      (node (ref "IC5") (pin "5") (pinfunction "NC_2_5") (pintype "passive"))
    )
    (net (code "48") (name "unconnected-(IC5-NC_3-Pad9)") (class "Default")
      (node (ref "IC5") (pin "9") (pinfunction "NC_3_9") (pintype "passive+no_connect"))
    )
    (net (code "49") (name "unconnected-(IC5-NC_4-Pad10)") (class "Default")
      (node (ref "IC5") (pin "10") (pinfunction "NC_4_10") (pintype "passive+no_connect"))
    )
    (net (code "50") (name "unconnected-(IC5-NC_5-Pad16)") (class "Default")
      (node (ref "IC5") (pin "16") (pinfunction "NC_5_16") (pintype "passive+no_connect"))
    )
    (net (code "51") (name "unconnected-(IC5-SD-Pad13)") (class "Default")
      (node (ref "IC5") (pin "13") (pinfunction "SD_13") (pintype "passive+no_connect"))
    )
    (net (code "52") (name "unconnected-(IC6-NC_1-Pad4)") (class "Default")
      (node (ref "IC6") (pin "4") (pinfunction "NC_1_4") (pintype "passive+no_connect"))
    )
    (net (code "53") (name "unconnected-(IC6-NC_2-Pad5)") (class "Default")
      (node (ref "IC6") (pin "5") (pinfunction "NC_2_5") (pintype "passive+no_connect"))
    )
    (net (code "54") (name "unconnected-(IC6-NC_3-Pad9)") (class "Default")
      (node (ref "IC6") (pin "9") (pinfunction "NC_3_9") (pintype "passive+no_connect"))
    )
    (net (code "55") (name "unconnected-(IC6-NC_4-Pad10)") (class "Default")
      (node (ref "IC6") (pin "10") (pinfunction "NC_4_10") (pintype "passive+no_connect"))
    )
    (net (code "56") (name "unconnected-(IC6-NC_5-Pad16)") (class "Default")
      (node (ref "IC6") (pin "16") (pinfunction "NC_5_16") (pintype "passive+no_connect"))
    )
    (net (code "57") (name "unconnected-(IC6-SD-Pad13)") (class "Default")
      (node (ref "IC6") (pin "13") (pinfunction "SD_13") (pintype "passive+no_connect"))
    )
    (net (code "58") (name "unconnected-(U8-NC-Pad4)") (class "Default")
      (node (ref "U8") (pin "4") (pinfunction "NC_4") (pintype "passive"))
    )
    (net (code "59") (name "unconnected-(U8-NC-Pad5)") (class "Default")
      (node (ref "U8") (pin "5") (pinfunction "NC_5") (pintype "passive"))
    )
    (net (code "60") (name "unconnected-(U8-NC-Pad7)") (class "Default")
      (node (ref "U8") (pin "7") (pinfunction "NC_7") (pintype "passive"))
    )
    (net (code "61") (name "unconnected-(U9-NC-Pad4)") (class "Default")
      (node (ref "U9") (pin "4") (pinfunction "NC_4") (pintype "passive"))
    )
    (net (code "62") (name "unconnected-(U9-NC-Pad5)") (class "Default")
      (node (ref "U9") (pin "5") (pinfunction "NC_5") (pintype "passive"))
    )
    (net (code "63") (name "unconnected-(U9-NC-Pad7)") (class "Default")
      (node (ref "U9") (pin "7") (pinfunction "NC_7") (pintype "passive"))
    )
  )
)
